# netSpeed.net
KiCad netlist of a schematic drawn in EAGLE
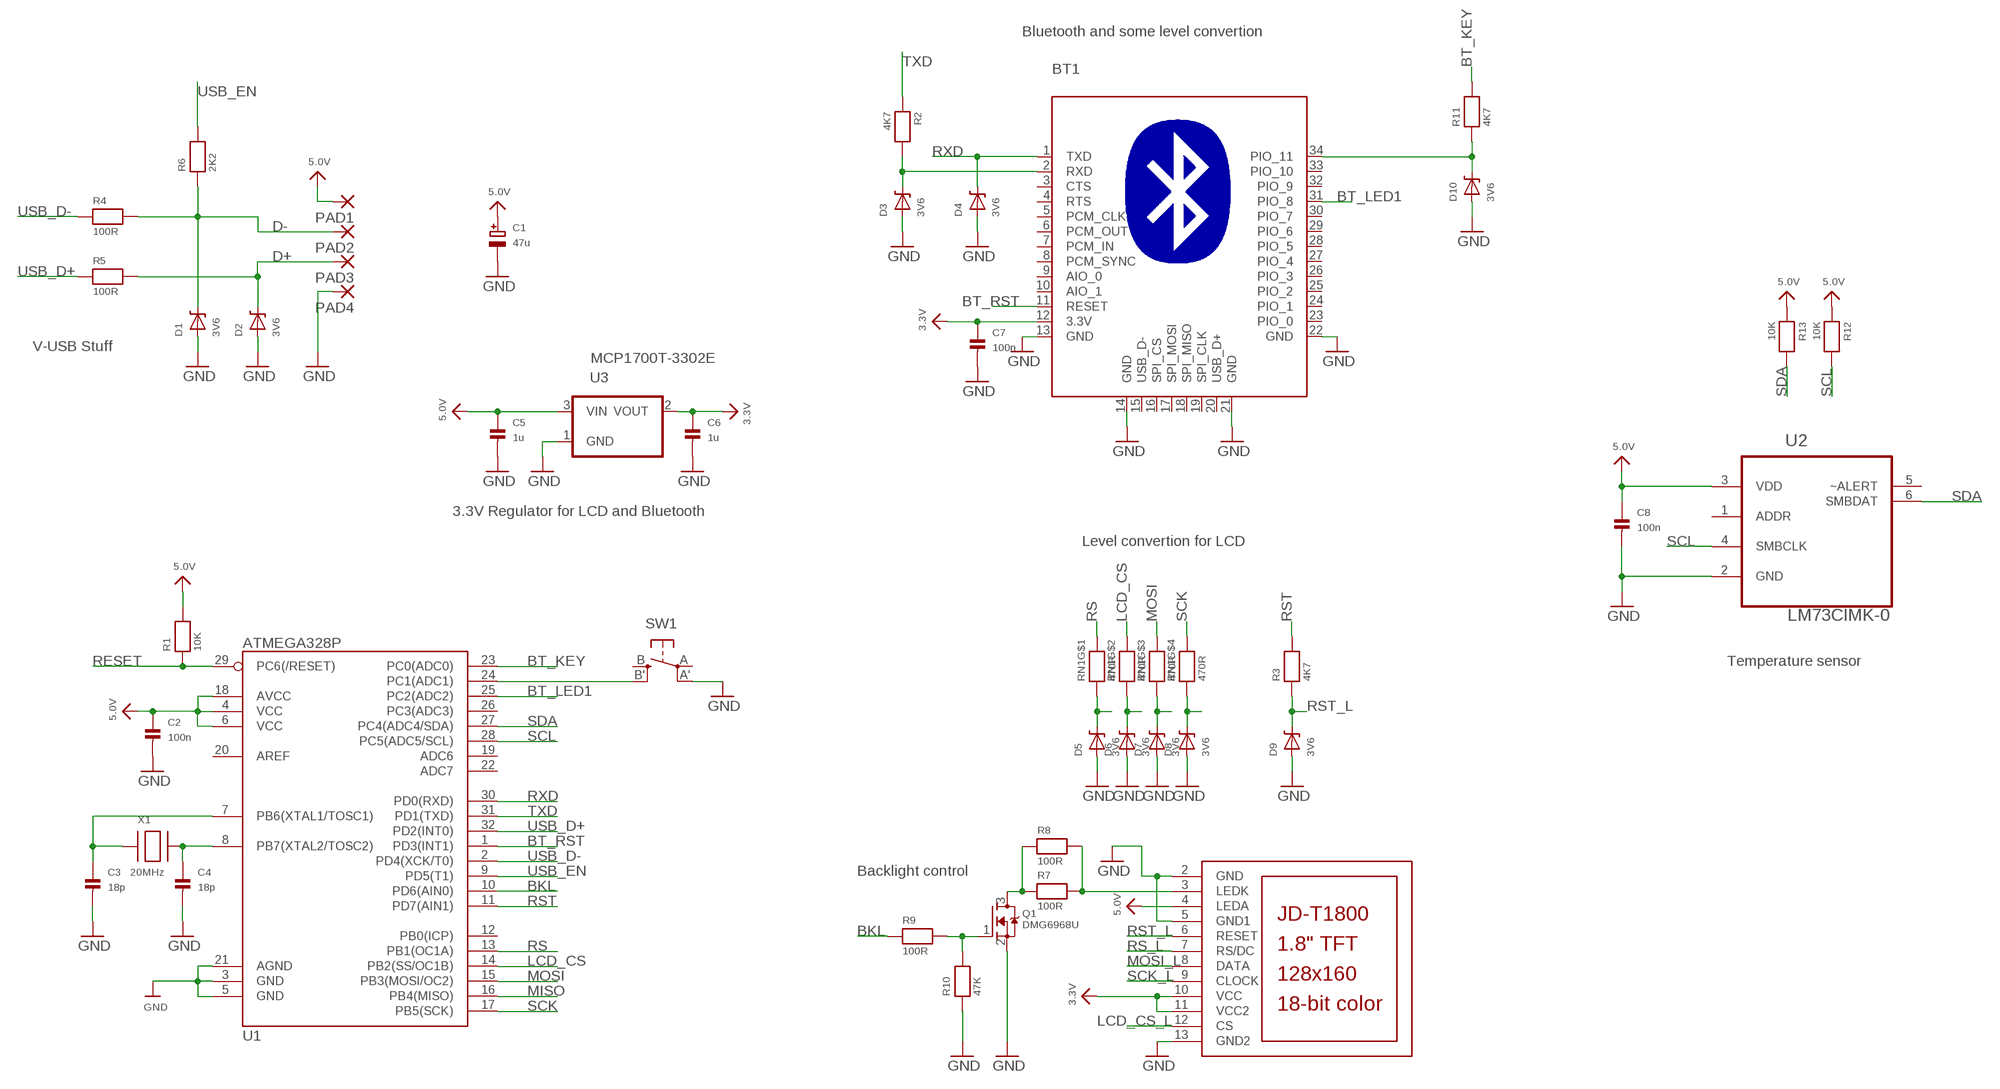
[diagram p0: schematic, sheet 1]

(export (version "E")
  (design (tool "Eeschema 10.0.6"))
  (components
    (comp (ref "BT1")
      (value "BLUETOOTH_MODULE")
      (footprint "eagle-import:BLUETOOTH_MODULE")
      (libsource (lib "eagle-import") (part "BLUETOOTH_MODULE"))
    )
    (comp (ref "C1")
      (value "47u")
      (footprint "eagle-import:PANASONIC_C")
      (libsource (lib "eagle-import") (part "CAP_ELECTROLYTICPANASONIC_C"))
    )
    (comp (ref "C2")
      (value "100n")
      (footprint "eagle-import:0805")
      (libsource (lib "eagle-import") (part "CAP_CERAMIC0805"))
    )
    (comp (ref "C3")
      (value "18p")
      (footprint "eagle-import:0805")
      (libsource (lib "eagle-import") (part "CAP_CERAMIC0805"))
    )
    (comp (ref "C4")
      (value "18p")
      (footprint "eagle-import:0805")
      (libsource (lib "eagle-import") (part "CAP_CERAMIC0805"))
    )
    (comp (ref "C5")
      (value "1u")
      (footprint "eagle-import:0805")
      (libsource (lib "eagle-import") (part "CAP_CERAMIC0805"))
    )
    (comp (ref "C6")
      (value "1u")
      (footprint "eagle-import:0805")
      (libsource (lib "eagle-import") (part "CAP_CERAMIC0805"))
    )
    (comp (ref "C7")
      (value "100n")
      (footprint "eagle-import:0805")
      (libsource (lib "eagle-import") (part "CAP_CERAMIC0805"))
    )
    (comp (ref "C8")
      (value "100n")
      (footprint "eagle-import:0805")
      (libsource (lib "eagle-import") (part "CAP_CERAMIC0805"))
    )
    (comp (ref "D1")
      (value "3V6")
      (footprint "eagle-import:SOD-323")
      (libsource (lib "eagle-import") (part "DIODE-ZENERSOD-323"))
    )
    (comp (ref "D2")
      (value "3V6")
      (footprint "eagle-import:SOD-323")
      (libsource (lib "eagle-import") (part "DIODE-ZENERSOD-323"))
    )
    (comp (ref "D3")
      (value "3V6")
      (footprint "eagle-import:SOD-323")
      (libsource (lib "eagle-import") (part "DIODE-ZENERSOD-323"))
    )
    (comp (ref "D4")
      (value "3V6")
      (footprint "eagle-import:SOD-323")
      (libsource (lib "eagle-import") (part "DIODE-ZENERSOD-323"))
    )
    (comp (ref "D5")
      (value "3V6")
      (footprint "eagle-import:SOD-323")
      (libsource (lib "eagle-import") (part "DIODE-ZENERSOD-323"))
    )
    (comp (ref "D6")
      (value "3V6")
      (footprint "eagle-import:SOD-323")
      (libsource (lib "eagle-import") (part "DIODE-ZENERSOD-323"))
    )
    (comp (ref "D7")
      (value "3V6")
      (footprint "eagle-import:SOD-323")
      (libsource (lib "eagle-import") (part "DIODE-ZENERSOD-323"))
    )
    (comp (ref "D8")
      (value "3V6")
      (footprint "eagle-import:SOD-323")
      (libsource (lib "eagle-import") (part "DIODE-ZENERSOD-323"))
    )
    (comp (ref "D9")
      (value "3V6")
      (footprint "eagle-import:SOD-323")
      (libsource (lib "eagle-import") (part "DIODE-ZENERSOD-323"))
    )
    (comp (ref "D10")
      (value "3V6")
      (footprint "eagle-import:SOD-323")
      (libsource (lib "eagle-import") (part "DIODE-ZENERSOD-323"))
    )
    (comp (ref "LCD1")
      (value "JD-T1800")
      (footprint "eagle-import:JD-T1800")
      (libsource (lib "eagle-import") (part "JD-T1800"))
    )
    (comp (ref "PAD1")
      (value "SMD2")
      (footprint "eagle-import:SMD1,27-2,54")
      (libsource (lib "eagle-import") (part "SMD2"))
    )
    (comp (ref "PAD2")
      (value "SMD2")
      (footprint "eagle-import:SMD1,27-2,54")
      (libsource (lib "eagle-import") (part "SMD2"))
    )
    (comp (ref "PAD3")
      (value "SMD2")
      (footprint "eagle-import:SMD1,27-2,54")
      (libsource (lib "eagle-import") (part "SMD2"))
    )
    (comp (ref "PAD4")
      (value "SMD2")
      (footprint "eagle-import:SMD1,27-2,54")
      (libsource (lib "eagle-import") (part "SMD2"))
    )
    (comp (ref "Q1")
      (value "DMG6968U")
      (footprint "eagle-import:SOT23-WIDE")
      (libsource (lib "eagle-import") (part "MOSFET-NWIDE"))
    )
    (comp (ref "R1")
      (value "10K")
      (footprint "eagle-import:0805")
      (libsource (lib "eagle-import") (part "RESISTOR0805"))
    )
    (comp (ref "R2")
      (value "4K7")
      (footprint "eagle-import:0805")
      (libsource (lib "eagle-import") (part "RESISTOR0805"))
    )
    (comp (ref "R3")
      (value "4K7")
      (footprint "eagle-import:0805")
      (libsource (lib "eagle-import") (part "RESISTOR0805"))
    )
    (comp (ref "R4")
      (value "100R")
      (footprint "eagle-import:0805")
      (libsource (lib "eagle-import") (part "RESISTOR0805"))
    )
    (comp (ref "R5")
      (value "100R")
      (footprint "eagle-import:0805")
      (libsource (lib "eagle-import") (part "RESISTOR0805"))
    )
    (comp (ref "R6")
      (value "2K2")
      (footprint "eagle-import:0805")
      (libsource (lib "eagle-import") (part "RESISTOR0805"))
    )
    (comp (ref "R7")
      (value "100R")
      (footprint "eagle-import:0805")
      (libsource (lib "eagle-import") (part "RESISTOR0805"))
    )
    (comp (ref "R8")
      (value "100R")
      (footprint "eagle-import:0805")
      (libsource (lib "eagle-import") (part "RESISTOR0805"))
    )
    (comp (ref "R9")
      (value "100R")
      (footprint "eagle-import:0805")
      (libsource (lib "eagle-import") (part "RESISTOR0805"))
    )
    (comp (ref "R10")
      (value "47K")
      (footprint "eagle-import:0805")
      (libsource (lib "eagle-import") (part "RESISTOR0805"))
    )
    (comp (ref "R11")
      (value "4K7")
      (footprint "eagle-import:0805")
      (libsource (lib "eagle-import") (part "RESISTOR0805"))
    )
    (comp (ref "R12")
      (value "10K")
      (footprint "eagle-import:0805")
      (libsource (lib "eagle-import") (part "RESISTOR0805"))
    )
    (comp (ref "R13")
      (value "10K")
      (footprint "eagle-import:0805")
      (libsource (lib "eagle-import") (part "RESISTOR0805"))
    )
    (comp (ref "RN1")
      (value "470R")
      (footprint "eagle-import:RESPACK_4X0603")
      (libsource (lib "eagle-import") (part "RESISTOR_4PACK"))
    )
    (comp (ref "SW1")
      (value "SPST_TACT")
      (footprint "eagle-import:TACT_SMD")
      (libsource (lib "eagle-import") (part "SPST_TACT"))
    )
    (comp (ref "U1")
      (value "ATMEGA328P")
      (footprint "eagle-import:TQFP32-08")
      (libsource (lib "eagle-import") (part "ATMEGA328_SMT"))
    )
    (comp (ref "U2")
      (value "LM73CIMK-0")
      (footprint "eagle-import:SOT95P285X100-6N")
      (libsource (lib "eagle-import") (part "LM73CIMK-0"))
    )
    (comp (ref "U3")
      (value "MCP1700T-3302E")
      (footprint "eagle-import:SOT-23")
      (libsource (lib "eagle-import") (part "MCP1700T-2502E/TTWIDE_PAD"))
    )
    (comp (ref "X1")
      (value "20MHz")
      (footprint "eagle-import:NX5032")
      (libsource (lib "eagle-import") (part "XTALNX5032"))
    )
  )
  (nets
    (net (code "1") (name "/BKL") (class "Default")
      (node (ref "R9") (pin "1") (pinfunction "1_1") (pintype "passive"))
      (node (ref "U1") (pin "10") (pinfunction "PD6(AIN0)_10") (pintype "bidirectional"))
    )
    (net (code "2") (name "/BT_KEY") (class "Default")
      (node (ref "R11") (pin "2") (pinfunction "2_2") (pintype "passive"))
      (node (ref "U1") (pin "23") (pinfunction "PC0(ADC0)_23") (pintype "bidirectional"))
    )
    (net (code "3") (name "/BT_LED1") (class "Default")
      (node (ref "BT1") (pin "31") (pinfunction "PIO_8_31") (pintype "bidirectional"))
      (node (ref "U1") (pin "25") (pinfunction "PC2(ADC2)_25") (pintype "bidirectional"))
    )
    (net (code "4") (name "/BT_RST") (class "Default")
      (node (ref "BT1") (pin "11") (pinfunction "RESET_11") (pintype "bidirectional"))
      (node (ref "U1") (pin "1") (pinfunction "PD3(INT1)_1") (pintype "bidirectional"))
    )
    (net (code "5") (name "/D+") (class "Default")
      (node (ref "D2") (pin "C") (pinfunction "C_C") (pintype "passive"))
      (node (ref "PAD3") (pin "1") (pinfunction "P_1") (pintype "passive"))
      (node (ref "R5") (pin "2") (pinfunction "2_2") (pintype "passive"))
    )
    (net (code "6") (name "/D-") (class "Default")
      (node (ref "D1") (pin "C") (pinfunction "C_C") (pintype "passive"))
      (node (ref "PAD2") (pin "1") (pinfunction "P_1") (pintype "passive"))
      (node (ref "R4") (pin "2") (pinfunction "2_2") (pintype "passive"))
      (node (ref "R6") (pin "1") (pinfunction "1_1") (pintype "passive"))
    )
    (net (code "7") (name "/LCD_CS") (class "Default")
      (node (ref "RN1") (pin "7") (pinfunction "2_7") (pintype "passive"))
      (node (ref "U1") (pin "14") (pinfunction "PB2(SS/OC1B)_14") (pintype "bidirectional"))
    )
    (net (code "8") (name "/LCD_CS_L") (class "Default")
      (node (ref "D6") (pin "C") (pinfunction "C_C") (pintype "passive"))
      (node (ref "LCD1") (pin "12") (pinfunction "CS_12") (pintype "input"))
      (node (ref "RN1") (pin "2") (pinfunction "1_2") (pintype "passive"))
    )
    (net (code "9") (name "/MISO") (class "Default")
      (node (ref "U1") (pin "16") (pinfunction "PB4(MISO)_16") (pintype "bidirectional"))
    )
    (net (code "10") (name "/MOSI") (class "Default")
      (node (ref "RN1") (pin "6") (pinfunction "2_6") (pintype "passive"))
      (node (ref "U1") (pin "15") (pinfunction "PB3(MOSI/OC2)_15") (pintype "bidirectional"))
    )
    (net (code "11") (name "/MOSI_L") (class "Default")
      (node (ref "D7") (pin "C") (pinfunction "C_C") (pintype "passive"))
      (node (ref "LCD1") (pin "8") (pinfunction "DATA_8") (pintype "bidirectional"))
      (node (ref "RN1") (pin "3") (pinfunction "1_3") (pintype "passive"))
    )
    (net (code "12") (name "/RESET") (class "Default")
      (node (ref "R1") (pin "1") (pinfunction "1_1") (pintype "passive"))
      (node (ref "U1") (pin "29") (pinfunction "PC6(/RESET)_29") (pintype "bidirectional"))
    )
    (net (code "13") (name "/RS") (class "Default")
      (node (ref "RN1") (pin "8") (pinfunction "2_8") (pintype "passive"))
      (node (ref "U1") (pin "13") (pinfunction "PB1(OC1A)_13") (pintype "bidirectional"))
    )
    (net (code "14") (name "/RST") (class "Default")
      (node (ref "R3") (pin "2") (pinfunction "2_2") (pintype "passive"))
      (node (ref "U1") (pin "11") (pinfunction "PD7(AIN1)_11") (pintype "bidirectional"))
    )
    (net (code "15") (name "/RST_L") (class "Default")
      (node (ref "D9") (pin "C") (pinfunction "C_C") (pintype "passive"))
      (node (ref "LCD1") (pin "6") (pinfunction "RESET_6") (pintype "input"))
      (node (ref "R3") (pin "1") (pinfunction "1_1") (pintype "passive"))
    )
    (net (code "16") (name "/RS_L") (class "Default")
      (node (ref "D5") (pin "C") (pinfunction "C_C") (pintype "passive"))
      (node (ref "LCD1") (pin "7") (pinfunction "RS/DC_7") (pintype "input"))
      (node (ref "RN1") (pin "1") (pinfunction "1_1") (pintype "passive"))
    )
    (net (code "17") (name "/RXD") (class "Default")
      (node (ref "BT1") (pin "1") (pinfunction "TXD_1") (pintype "bidirectional"))
      (node (ref "D4") (pin "C") (pinfunction "C_C") (pintype "passive"))
      (node (ref "U1") (pin "30") (pinfunction "PD0(RXD)_30") (pintype "bidirectional"))
    )
    (net (code "18") (name "/SCK") (class "Default")
      (node (ref "RN1") (pin "5") (pinfunction "2_5") (pintype "passive"))
      (node (ref "U1") (pin "17") (pinfunction "PB5(SCK)_17") (pintype "bidirectional"))
    )
    (net (code "19") (name "/SCK_L") (class "Default")
      (node (ref "D8") (pin "C") (pinfunction "C_C") (pintype "passive"))
      (node (ref "LCD1") (pin "9") (pinfunction "CLOCK_9") (pintype "input"))
      (node (ref "RN1") (pin "4") (pinfunction "1_4") (pintype "passive"))
    )
    (net (code "20") (name "/SCL") (class "Default")
      (node (ref "R12") (pin "2") (pinfunction "2_2") (pintype "passive"))
      (node (ref "U1") (pin "28") (pinfunction "PC5(ADC5/SCL)_28") (pintype "bidirectional"))
      (node (ref "U2") (pin "4") (pinfunction "SMBCLK_4") (pintype "input"))
    )
    (net (code "21") (name "/SDA") (class "Default")
      (node (ref "R13") (pin "2") (pinfunction "2_2") (pintype "passive"))
      (node (ref "U1") (pin "27") (pinfunction "PC4(ADC4/SDA)_27") (pintype "bidirectional"))
      (node (ref "U2") (pin "6") (pinfunction "SMBDAT_6") (pintype "output"))
    )
    (net (code "22") (name "/TXD") (class "Default")
      (node (ref "R2") (pin "1") (pinfunction "1_1") (pintype "passive"))
      (node (ref "U1") (pin "31") (pinfunction "PD1(TXD)_31") (pintype "bidirectional"))
    )
    (net (code "23") (name "/USB_D+") (class "Default")
      (node (ref "R5") (pin "1") (pinfunction "1_1") (pintype "passive"))
      (node (ref "U1") (pin "32") (pinfunction "PD2(INT0)_32") (pintype "bidirectional"))
    )
    (net (code "24") (name "/USB_D-") (class "Default")
      (node (ref "R4") (pin "1") (pinfunction "1_1") (pintype "passive"))
      (node (ref "U1") (pin "2") (pinfunction "PD4(XCK/T0)_2") (pintype "bidirectional"))
    )
    (net (code "25") (name "/USB_EN") (class "Default")
      (node (ref "R6") (pin "2") (pinfunction "2_2") (pintype "passive"))
      (node (ref "U1") (pin "9") (pinfunction "PD5(T1)_9") (pintype "bidirectional"))
    )
    (net (code "26") (name "3.3V") (class "Default")
      (node (ref "BT1") (pin "12") (pinfunction "3.3V_12") (pintype "power_in"))
      (node (ref "C6") (pin "1") (pinfunction "P$1_1") (pintype "passive"))
      (node (ref "C7") (pin "1") (pinfunction "P$1_1") (pintype "passive"))
      (node (ref "LCD1") (pin "10") (pinfunction "VCC_10") (pintype "power_in"))
      (node (ref "LCD1") (pin "11") (pinfunction "VCC2_11") (pintype "power_in"))
      (node (ref "U3") (pin "2") (pinfunction "VOUT_2") (pintype "output"))
    )
    (net (code "27") (name "5.0V") (class "Default")
      (node (ref "C1") (pin "+") (pinfunction "+_+") (pintype "passive"))
      (node (ref "C2") (pin "1") (pinfunction "P$1_1") (pintype "passive"))
      (node (ref "C5") (pin "1") (pinfunction "P$1_1") (pintype "passive"))
      (node (ref "C8") (pin "1") (pinfunction "P$1_1") (pintype "passive"))
      (node (ref "LCD1") (pin "4") (pinfunction "LEDA_4") (pintype "input"))
      (node (ref "PAD1") (pin "1") (pinfunction "P_1") (pintype "passive"))
      (node (ref "R1") (pin "2") (pinfunction "2_2") (pintype "passive"))
      (node (ref "R12") (pin "1") (pinfunction "1_1") (pintype "passive"))
      (node (ref "R13") (pin "1") (pinfunction "1_1") (pintype "passive"))
      (node (ref "U1") (pin "18") (pinfunction "AVCC_18") (pintype "bidirectional"))
      (node (ref "U1") (pin "4") (pinfunction "VCC_4") (pintype "bidirectional"))
      (node (ref "U1") (pin "6") (pinfunction "VCC_6") (pintype "bidirectional"))
      (node (ref "U2") (pin "3") (pinfunction "VDD_3") (pintype "power_in"))
      (node (ref "U3") (pin "3") (pinfunction "VIN_3") (pintype "power_in"))
    )
    (net (code "28") (name "GND") (class "Default")
      (node (ref "BT1") (pin "13") (pinfunction "GND_13") (pintype "power_in"))
      (node (ref "BT1") (pin "14") (pinfunction "GND_14") (pintype "power_in"))
      (node (ref "BT1") (pin "21") (pinfunction "GND_21") (pintype "power_in"))
      (node (ref "BT1") (pin "22") (pinfunction "GND_22") (pintype "power_in"))
      (node (ref "C1") (pin "-") (pinfunction "-_-") (pintype "passive"))
      (node (ref "C2") (pin "2") (pinfunction "P$2_2") (pintype "passive"))
      (node (ref "C3") (pin "2") (pinfunction "P$2_2") (pintype "passive"))
      (node (ref "C4") (pin "2") (pinfunction "P$2_2") (pintype "passive"))
      (node (ref "C5") (pin "2") (pinfunction "P$2_2") (pintype "passive"))
      (node (ref "C6") (pin "2") (pinfunction "P$2_2") (pintype "passive"))
      (node (ref "C7") (pin "2") (pinfunction "P$2_2") (pintype "passive"))
      (node (ref "C8") (pin "2") (pinfunction "P$2_2") (pintype "passive"))
      (node (ref "D1") (pin "A") (pinfunction "A_A") (pintype "passive"))
      (node (ref "D10") (pin "A") (pinfunction "A_A") (pintype "passive"))
      (node (ref "D2") (pin "A") (pinfunction "A_A") (pintype "passive"))
      (node (ref "D3") (pin "A") (pinfunction "A_A") (pintype "passive"))
      (node (ref "D4") (pin "A") (pinfunction "A_A") (pintype "passive"))
      (node (ref "D5") (pin "A") (pinfunction "A_A") (pintype "passive"))
      (node (ref "D6") (pin "A") (pinfunction "A_A") (pintype "passive"))
      (node (ref "D7") (pin "A") (pinfunction "A_A") (pintype "passive"))
      (node (ref "D8") (pin "A") (pinfunction "A_A") (pintype "passive"))
      (node (ref "D9") (pin "A") (pinfunction "A_A") (pintype "passive"))
      (node (ref "LCD1") (pin "13") (pinfunction "GND2_13") (pintype "power_in"))
      (node (ref "LCD1") (pin "2") (pinfunction "GND_2") (pintype "power_in"))
      (node (ref "LCD1") (pin "5") (pinfunction "GND1_5") (pintype "power_in"))
      (node (ref "PAD4") (pin "1") (pinfunction "P_1") (pintype "passive"))
      (node (ref "Q1") (pin "2") (pinfunction "S_2") (pintype "bidirectional"))
      (node (ref "R10") (pin "1") (pinfunction "1_1") (pintype "passive"))
      (node (ref "SW1") (pin "A'") (pinfunction "P1_A'") (pintype "passive"))
      (node (ref "U1") (pin "21") (pinfunction "AGND_21") (pintype "bidirectional"))
      (node (ref "U1") (pin "3") (pinfunction "GND_3") (pintype "bidirectional"))
      (node (ref "U1") (pin "5") (pinfunction "GND_5") (pintype "bidirectional"))
      (node (ref "U2") (pin "2") (pinfunction "GND_2") (pintype "passive"))
      (node (ref "U3") (pin "1") (pinfunction "GND_1") (pintype "passive"))
    )
    (net (code "29") (name "Net-(BT1-PIO_11)") (class "Default")
      (node (ref "BT1") (pin "34") (pinfunction "PIO_11_34") (pintype "bidirectional"))
      (node (ref "D10") (pin "C") (pinfunction "C_C") (pintype "passive"))
      (node (ref "R11") (pin "1") (pinfunction "1_1") (pintype "passive"))
    )
    (net (code "30") (name "Net-(BT1-RXD)") (class "Default")
      (node (ref "BT1") (pin "2") (pinfunction "RXD_2") (pintype "bidirectional"))
      (node (ref "D3") (pin "C") (pinfunction "C_C") (pintype "passive"))
      (node (ref "R2") (pin "2") (pinfunction "2_2") (pintype "passive"))
    )
    (net (code "31") (name "Net-(C3-P$1)") (class "Default")
      (node (ref "C3") (pin "1") (pinfunction "P$1_1") (pintype "passive"))
      (node (ref "U1") (pin "7") (pinfunction "PB6(XTAL1/TOSC1)_7") (pintype "bidirectional"))
      (node (ref "X1") (pin "P$1") (pinfunction "P$1_P$1") (pintype "bidirectional"))
    )
    (net (code "32") (name "Net-(C4-P$1)") (class "Default")
      (node (ref "C4") (pin "1") (pinfunction "P$1_1") (pintype "passive"))
      (node (ref "U1") (pin "8") (pinfunction "PB7(XTAL2/TOSC2)_8") (pintype "bidirectional"))
      (node (ref "X1") (pin "P$2") (pinfunction "P$2_P$2") (pintype "bidirectional"))
    )
    (net (code "33") (name "Net-(LCD1-LEDK)") (class "Default")
      (node (ref "LCD1") (pin "3") (pinfunction "LEDK_3") (pintype "input"))
      (node (ref "R7") (pin "2") (pinfunction "2_2") (pintype "passive"))
      (node (ref "R8") (pin "2") (pinfunction "2_2") (pintype "passive"))
    )
    (net (code "34") (name "Net-(Q1-D)") (class "Default")
      (node (ref "Q1") (pin "3") (pinfunction "D_3") (pintype "bidirectional"))
      (node (ref "R7") (pin "1") (pinfunction "1_1") (pintype "passive"))
      (node (ref "R8") (pin "1") (pinfunction "1_1") (pintype "passive"))
    )
    (net (code "35") (name "Net-(Q1-G)") (class "Default")
      (node (ref "Q1") (pin "1") (pinfunction "G_1") (pintype "bidirectional"))
      (node (ref "R10") (pin "2") (pinfunction "2_2") (pintype "passive"))
      (node (ref "R9") (pin "2") (pinfunction "2_2") (pintype "passive"))
    )
    (net (code "36") (name "Net-(SW1-S1)") (class "Default")
      (node (ref "SW1") (pin "B'") (pinfunction "S1_B'") (pintype "passive"))
      (node (ref "U1") (pin "24") (pinfunction "PC1(ADC1)_24") (pintype "bidirectional"))
    )
    (net (code "37") (name "unconnected-(BT1-AIO_0-Pad9)") (class "Default")
      (node (ref "BT1") (pin "9") (pinfunction "AIO_0_9") (pintype "bidirectional"))
    )
    (net (code "38") (name "unconnected-(BT1-AIO_1-Pad10)") (class "Default")
      (node (ref "BT1") (pin "10") (pinfunction "AIO_1_10") (pintype "bidirectional"))
    )
    (net (code "39") (name "unconnected-(BT1-CTS-Pad3)") (class "Default")
      (node (ref "BT1") (pin "3") (pinfunction "CTS_3") (pintype "bidirectional"))
    )
    (net (code "40") (name "unconnected-(BT1-PCM_CLK-Pad5)") (class "Default")
      (node (ref "BT1") (pin "5") (pinfunction "PCM_CLK_5") (pintype "bidirectional"))
    )
    (net (code "41") (name "unconnected-(BT1-PCM_IN-Pad7)") (class "Default")
      (node (ref "BT1") (pin "7") (pinfunction "PCM_IN_7") (pintype "bidirectional"))
    )
    (net (code "42") (name "unconnected-(BT1-PCM_OUT-Pad6)") (class "Default")
      (node (ref "BT1") (pin "6") (pinfunction "PCM_OUT_6") (pintype "bidirectional"))
    )
    (net (code "43") (name "unconnected-(BT1-PCM_SYNC-Pad8)") (class "Default")
      (node (ref "BT1") (pin "8") (pinfunction "PCM_SYNC_8") (pintype "bidirectional"))
    )
    (net (code "44") (name "unconnected-(BT1-PIO_0-Pad23)") (class "Default")
      (node (ref "BT1") (pin "23") (pinfunction "PIO_0_23") (pintype "bidirectional"))
    )
    (net (code "45") (name "unconnected-(BT1-PIO_1-Pad24)") (class "Default")
      (node (ref "BT1") (pin "24") (pinfunction "PIO_1_24") (pintype "bidirectional"))
    )
    (net (code "46") (name "unconnected-(BT1-PIO_2-Pad25)") (class "Default")
      (node (ref "BT1") (pin "25") (pinfunction "PIO_2_25") (pintype "bidirectional"))
    )
    (net (code "47") (name "unconnected-(BT1-PIO_3-Pad26)") (class "Default")
      (node (ref "BT1") (pin "26") (pinfunction "PIO_3_26") (pintype "bidirectional"))
    )
    (net (code "48") (name "unconnected-(BT1-PIO_4-Pad27)") (class "Default")
      (node (ref "BT1") (pin "27") (pinfunction "PIO_4_27") (pintype "bidirectional"))
    )
    (net (code "49") (name "unconnected-(BT1-PIO_5-Pad28)") (class "Default")
      (node (ref "BT1") (pin "28") (pinfunction "PIO_5_28") (pintype "bidirectional"))
    )
    (net (code "50") (name "unconnected-(BT1-PIO_6-Pad29)") (class "Default")
      (node (ref "BT1") (pin "29") (pinfunction "PIO_6_29") (pintype "bidirectional"))
    )
    (net (code "51") (name "unconnected-(BT1-PIO_7-Pad30)") (class "Default")
      (node (ref "BT1") (pin "30") (pinfunction "PIO_7_30") (pintype "bidirectional"))
    )
    (net (code "52") (name "unconnected-(BT1-PIO_9-Pad32)") (class "Default")
      (node (ref "BT1") (pin "32") (pinfunction "PIO_9_32") (pintype "bidirectional"))
    )
    (net (code "53") (name "unconnected-(BT1-PIO_10-Pad33)") (class "Default")
      (node (ref "BT1") (pin "33") (pinfunction "PIO_10_33") (pintype "bidirectional"))
    )
    (net (code "54") (name "unconnected-(BT1-RTS-Pad4)") (class "Default")
      (node (ref "BT1") (pin "4") (pinfunction "RTS_4") (pintype "bidirectional"))
    )
    (net (code "55") (name "unconnected-(BT1-SPI_CLK-Pad19)") (class "Default")
      (node (ref "BT1") (pin "19") (pinfunction "SPI_CLK_19") (pintype "bidirectional"))
    )
    (net (code "56") (name "unconnected-(BT1-SPI_CS-Pad16)") (class "Default")
      (node (ref "BT1") (pin "16") (pinfunction "SPI_CS_16") (pintype "bidirectional"))
    )
    (net (code "57") (name "unconnected-(BT1-SPI_MISO-Pad18)") (class "Default")
      (node (ref "BT1") (pin "18") (pinfunction "SPI_MISO_18") (pintype "bidirectional"))
    )
    (net (code "58") (name "unconnected-(BT1-SPI_MOSI-Pad17)") (class "Default")
      (node (ref "BT1") (pin "17") (pinfunction "SPI_MOSI_17") (pintype "bidirectional"))
    )
    (net (code "59") (name "unconnected-(BT1-USB_D+-Pad20)") (class "Default")
      (node (ref "BT1") (pin "20") (pinfunction "USB_D+_20") (pintype "bidirectional"))
    )
    (net (code "60") (name "unconnected-(BT1-USB_D--Pad15)") (class "Default")
      (node (ref "BT1") (pin "15") (pinfunction "USB_D-_15") (pintype "bidirectional"))
    )
    (net (code "61") (name "unconnected-(SW1-P-PadA)") (class "Default")
      (node (ref "SW1") (pin "A") (pinfunction "P_A") (pintype "passive"))
    )
    (net (code "62") (name "unconnected-(SW1-S-PadB)") (class "Default")
      (node (ref "SW1") (pin "B") (pinfunction "S_B") (pintype "passive"))
    )
    (net (code "63") (name "unconnected-(U1-ADC6-Pad19)") (class "Default")
      (node (ref "U1") (pin "19") (pinfunction "ADC6_19") (pintype "bidirectional"))
    )
    (net (code "64") (name "unconnected-(U1-ADC7-Pad22)") (class "Default")
      (node (ref "U1") (pin "22") (pinfunction "ADC7_22") (pintype "bidirectional"))
    )
    (net (code "65") (name "unconnected-(U1-AREF-Pad20)") (class "Default")
      (node (ref "U1") (pin "20") (pinfunction "AREF_20") (pintype "bidirectional"))
    )
    (net (code "66") (name "unconnected-(U1-PB0(ICP)-Pad12)") (class "Default")
      (node (ref "U1") (pin "12") (pinfunction "PB0(ICP)_12") (pintype "bidirectional"))
    )
    (net (code "67") (name "unconnected-(U1-PC3(ADC3)-Pad26)") (class "Default")
      (node (ref "U1") (pin "26") (pinfunction "PC3(ADC3)_26") (pintype "bidirectional"))
    )
    (net (code "68") (name "unconnected-(U2-ADDR-Pad1)") (class "Default")
      (node (ref "U2") (pin "1") (pinfunction "ADDR_1") (pintype "input"))
    )
    (net (code "69") (name "unconnected-(U2-~{ALERT}-Pad5)") (class "Default")
      (node (ref "U2") (pin "5") (pinfunction "~{ALERT}_5") (pintype "output"))
    )
  )
)
